# MakePython_Audio_v2_0.net
KiCad netlist of a schematic drawn in EAGLE
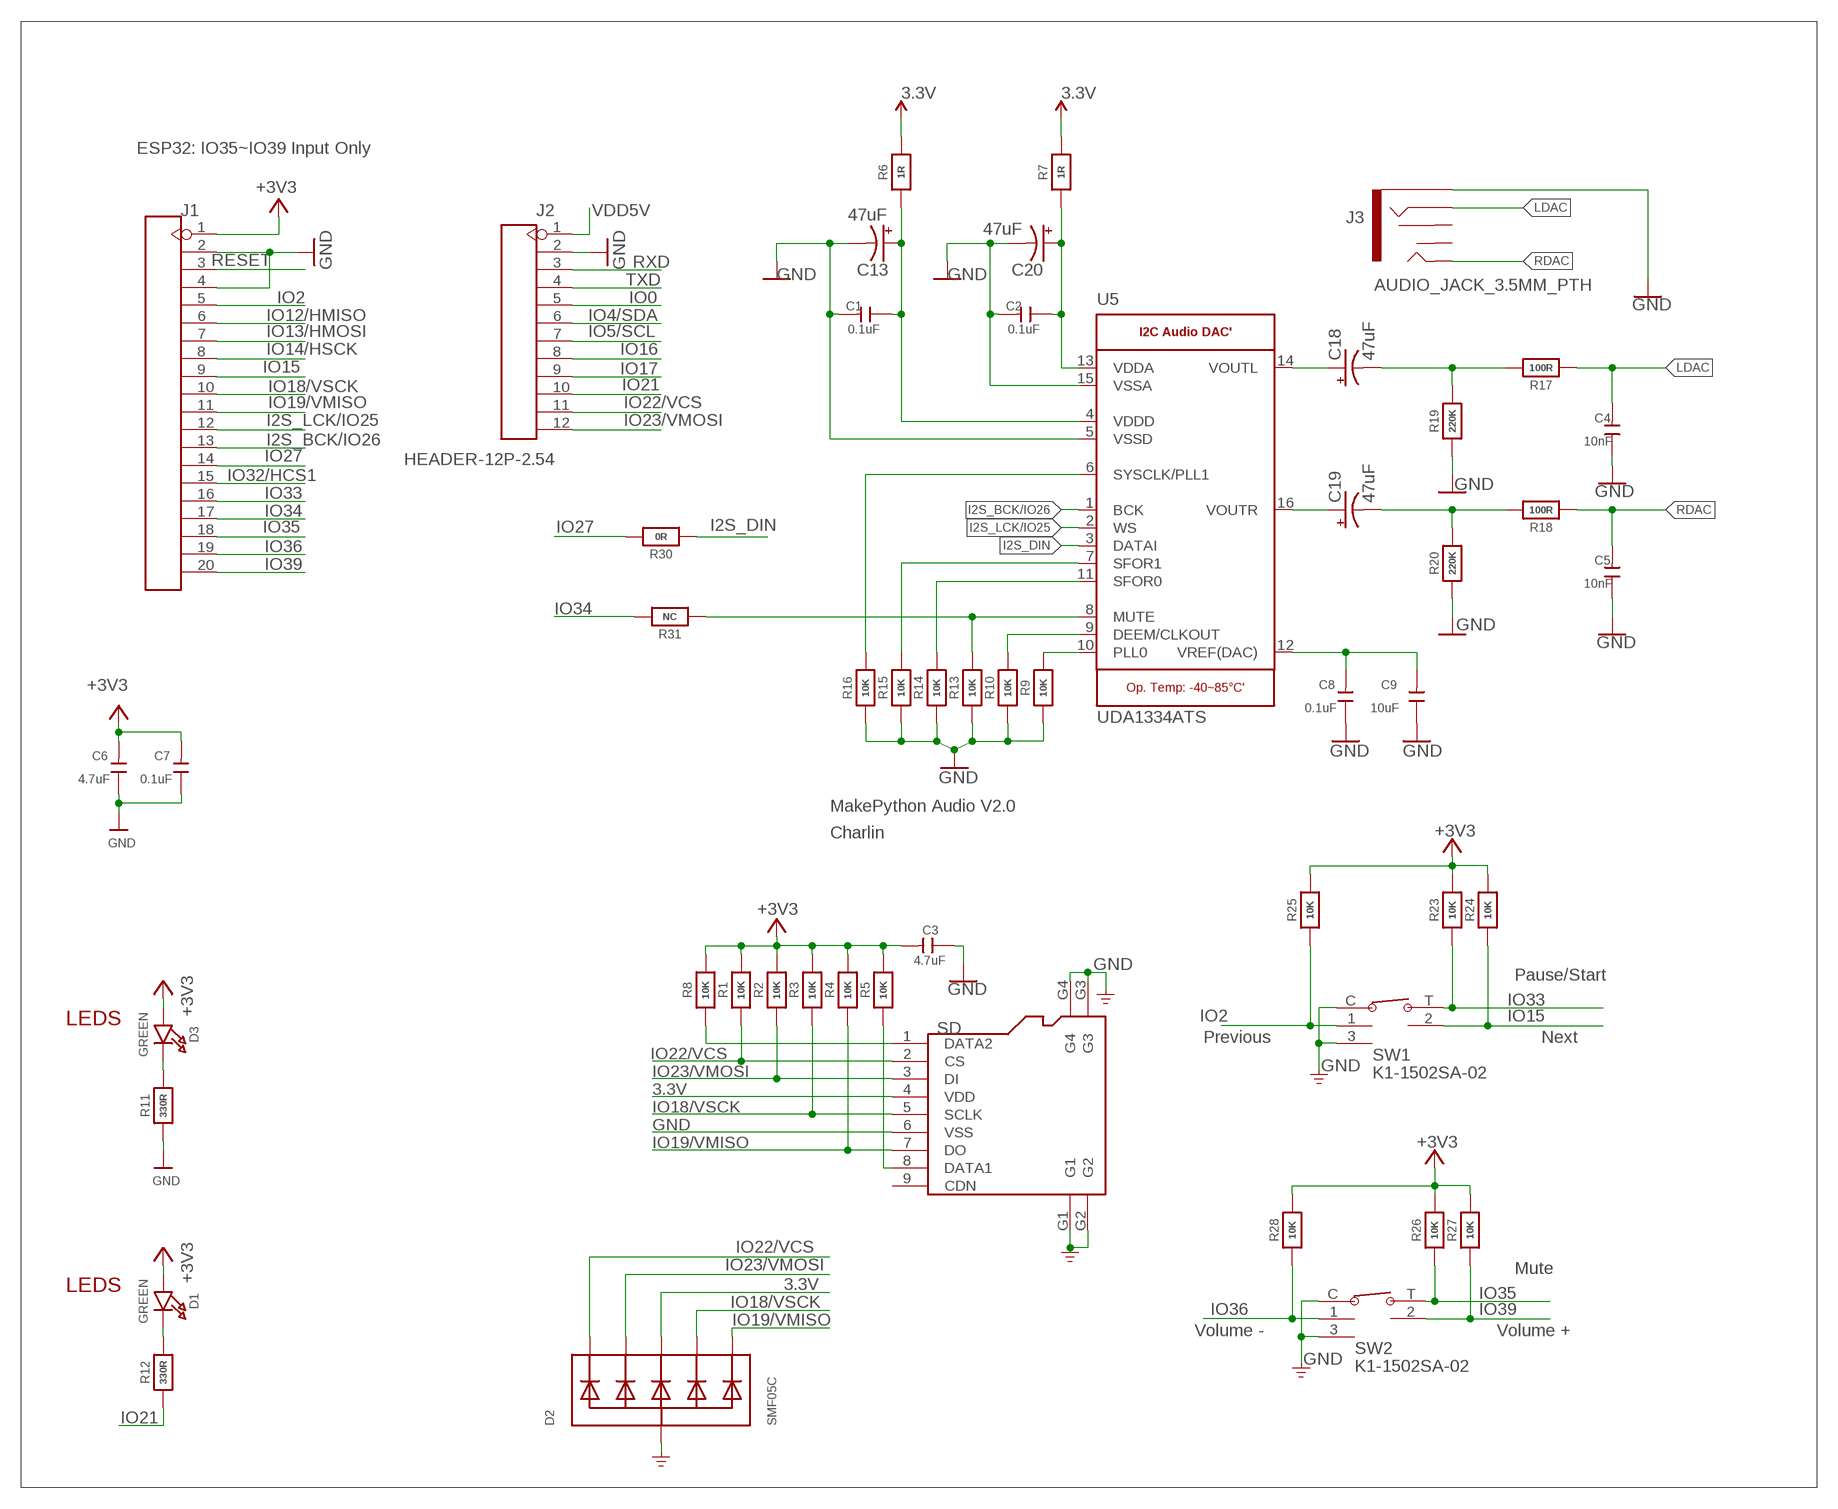
[diagram p0: schematic, sheet 1]

(export (version "E")
  (design (tool "Eeschema 10.0.6"))
  (components
    (comp (ref "C1")
      (value "0.1uF")
      (footprint "eagle-import:DISCRETE_C0603")
      (libsource (lib "eagle-import") (part "DISCRETE_C-0603"))
    )
    (comp (ref "C2")
      (value "0.1uF")
      (footprint "eagle-import:DISCRETE_C0603")
      (libsource (lib "eagle-import") (part "DISCRETE_C-0603"))
    )
    (comp (ref "C3")
      (value "4.7uF")
      (footprint "eagle-import:DISCRETE_C0603")
      (libsource (lib "eagle-import") (part "DISCRETE_C-0603"))
    )
    (comp (ref "C4")
      (value "10nF")
      (footprint "eagle-import:DISCRETE_C0603")
      (libsource (lib "eagle-import") (part "DISCRETE_C-0603"))
    )
    (comp (ref "C5")
      (value "10nF")
      (footprint "eagle-import:DISCRETE_C0603")
      (libsource (lib "eagle-import") (part "DISCRETE_C-0603"))
    )
    (comp (ref "C6")
      (value "4.7uF")
      (footprint "eagle-import:DISCRETE_C0603")
      (libsource (lib "eagle-import") (part "DISCRETE_C-0603"))
    )
    (comp (ref "C7")
      (value "0.1uF")
      (footprint "eagle-import:DISCRETE_C0603")
      (libsource (lib "eagle-import") (part "DISCRETE_C-0603"))
    )
    (comp (ref "C8")
      (value "0.1uF")
      (footprint "eagle-import:DISCRETE_C0603")
      (libsource (lib "eagle-import") (part "DISCRETE_C-0603"))
    )
    (comp (ref "C9")
      (value "10uF")
      (footprint "eagle-import:DISCRETE_C0603")
      (libsource (lib "eagle-import") (part "DISCRETE_C-0603"))
    )
    (comp (ref "C13")
      (value "47uF")
      (footprint "eagle-import:EIA3528")
      (libsource (lib "eagle-import") (part "47UF-POLAR-EIA3528-10V-10%"))
    )
    (comp (ref "C18")
      (value "47uF")
      (footprint "eagle-import:EIA3528")
      (libsource (lib "eagle-import") (part "47UF-POLAR-EIA3528-10V-10%"))
    )
    (comp (ref "C19")
      (value "47uF")
      (footprint "eagle-import:EIA3528")
      (libsource (lib "eagle-import") (part "47UF-POLAR-EIA3528-10V-10%"))
    )
    (comp (ref "C20")
      (value "47uF")
      (footprint "eagle-import:EIA3528")
      (libsource (lib "eagle-import") (part "47UF-POLAR-EIA3528-10V-10%"))
    )
    (comp (ref "D1")
      (value "GREEN")
      (footprint "eagle-import:CHIPLED_0805_NOOUTLINE")
      (libsource (lib "eagle-import") (part "LED0805_NOOUTLINE"))
    )
    (comp (ref "D2")
      (value "SMF05C")
      (footprint "eagle-import:SOT363")
      (libsource (lib "eagle-import") (part "TVSARRAY_5LANE"))
    )
    (comp (ref "D3")
      (value "GREEN")
      (footprint "eagle-import:CHIPLED_0805_NOOUTLINE")
      (libsource (lib "eagle-import") (part "LED0805_NOOUTLINE"))
    )
    (comp (ref "J1")
      (value "HEADER-20P-2.54")
      (footprint "eagle-import:20P-2.54")
      (libsource (lib "eagle-import") (part "HEADER-20P-2.54"))
    )
    (comp (ref "J2")
      (value "HEADER-12P-2.54")
      (footprint "eagle-import:12P-2.54")
      (libsource (lib "eagle-import") (part "HEADER-12P-2.54"))
    )
    (comp (ref "J3")
      (value "AUDIO_JACK_3.5MM_PTH")
      (footprint "eagle-import:AUDIO-JACK")
      (libsource (lib "eagle-import") (part "AUDIO_JACK_3.5MM_PTH"))
    )
    (comp (ref "R1")
      (value "10K")
      (footprint "eagle-import:0603-NO")
      (libsource (lib "eagle-import") (part "RESISTOR_0603_NOOUT"))
    )
    (comp (ref "R2")
      (value "10K")
      (footprint "eagle-import:0603-NO")
      (libsource (lib "eagle-import") (part "RESISTOR_0603_NOOUT"))
    )
    (comp (ref "R3")
      (value "10K")
      (footprint "eagle-import:0603-NO")
      (libsource (lib "eagle-import") (part "RESISTOR_0603_NOOUT"))
    )
    (comp (ref "R4")
      (value "10K")
      (footprint "eagle-import:0603-NO")
      (libsource (lib "eagle-import") (part "RESISTOR_0603_NOOUT"))
    )
    (comp (ref "R5")
      (value "10K")
      (footprint "eagle-import:0603-NO")
      (libsource (lib "eagle-import") (part "RESISTOR_0603_NOOUT"))
    )
    (comp (ref "R6")
      (value "1R")
      (footprint "eagle-import:0603-NO")
      (libsource (lib "eagle-import") (part "RESISTOR_0603_NOOUT"))
    )
    (comp (ref "R7")
      (value "1R")
      (footprint "eagle-import:0603-NO")
      (libsource (lib "eagle-import") (part "RESISTOR_0603_NOOUT"))
    )
    (comp (ref "R8")
      (value "10K")
      (footprint "eagle-import:0603-NO")
      (libsource (lib "eagle-import") (part "RESISTOR_0603_NOOUT"))
    )
    (comp (ref "R9")
      (value "10K")
      (footprint "eagle-import:0603-NO")
      (libsource (lib "eagle-import") (part "RESISTOR_0603_NOOUT"))
    )
    (comp (ref "R10")
      (value "10K")
      (footprint "eagle-import:0603-NO")
      (libsource (lib "eagle-import") (part "RESISTOR_0603_NOOUT"))
    )
    (comp (ref "R11")
      (value "330R")
      (footprint "eagle-import:0603-NO")
      (libsource (lib "eagle-import") (part "RESISTOR_0603_NOOUT"))
    )
    (comp (ref "R12")
      (value "330R")
      (footprint "eagle-import:0603-NO")
      (libsource (lib "eagle-import") (part "RESISTOR_0603_NOOUT"))
    )
    (comp (ref "R13")
      (value "10K")
      (footprint "eagle-import:0603-NO")
      (libsource (lib "eagle-import") (part "RESISTOR_0603_NOOUT"))
    )
    (comp (ref "R14")
      (value "10K")
      (footprint "eagle-import:0603-NO")
      (libsource (lib "eagle-import") (part "RESISTOR_0603_NOOUT"))
    )
    (comp (ref "R15")
      (value "10K")
      (footprint "eagle-import:0603-NO")
      (libsource (lib "eagle-import") (part "RESISTOR_0603_NOOUT"))
    )
    (comp (ref "R16")
      (value "10K")
      (footprint "eagle-import:0603-NO")
      (libsource (lib "eagle-import") (part "RESISTOR_0603_NOOUT"))
    )
    (comp (ref "R17")
      (value "100R")
      (footprint "eagle-import:0603-NO")
      (libsource (lib "eagle-import") (part "RESISTOR_0603_NOOUT"))
    )
    (comp (ref "R18")
      (value "100R")
      (footprint "eagle-import:0603-NO")
      (libsource (lib "eagle-import") (part "RESISTOR_0603_NOOUT"))
    )
    (comp (ref "R19")
      (value "220K")
      (footprint "eagle-import:0603-NO")
      (libsource (lib "eagle-import") (part "RESISTOR_0603_NOOUT"))
    )
    (comp (ref "R20")
      (value "220K")
      (footprint "eagle-import:0603-NO")
      (libsource (lib "eagle-import") (part "RESISTOR_0603_NOOUT"))
    )
    (comp (ref "R23")
      (value "10K")
      (footprint "eagle-import:0603-NO")
      (libsource (lib "eagle-import") (part "RESISTOR_0603_NOOUT"))
    )
    (comp (ref "R24")
      (value "10K")
      (footprint "eagle-import:0603-NO")
      (libsource (lib "eagle-import") (part "RESISTOR_0603_NOOUT"))
    )
    (comp (ref "R25")
      (value "10K")
      (footprint "eagle-import:0603-NO")
      (libsource (lib "eagle-import") (part "RESISTOR_0603_NOOUT"))
    )
    (comp (ref "R26")
      (value "10K")
      (footprint "eagle-import:0603-NO")
      (libsource (lib "eagle-import") (part "RESISTOR_0603_NOOUT"))
    )
    (comp (ref "R27")
      (value "10K")
      (footprint "eagle-import:0603-NO")
      (libsource (lib "eagle-import") (part "RESISTOR_0603_NOOUT"))
    )
    (comp (ref "R28")
      (value "10K")
      (footprint "eagle-import:0603-NO")
      (libsource (lib "eagle-import") (part "RESISTOR_0603_NOOUT"))
    )
    (comp (ref "R30")
      (value "0R")
      (footprint "eagle-import:0603-NO")
      (libsource (lib "eagle-import") (part "RESISTOR_0603_NOOUT"))
    )
    (comp (ref "R31")
      (value "NC")
      (footprint "eagle-import:0603-NO")
      (libsource (lib "eagle-import") (part "RESISTOR_0603_NOOUT"))
    )
    (comp (ref "SD")
      (value "HOLDER-MICROSD-9P")
      (footprint "eagle-import:9P-SMD-W_-RING")
      (libsource (lib "eagle-import") (part "HOLDER-MICROSD-9P"))
    )
    (comp (ref "SW1")
      (value "K1-1502SA-02")
      (footprint "eagle-import:SMD5-60P-1180L1170W")
      (libsource (lib "eagle-import") (part "K1-1502SA-02"))
    )
    (comp (ref "SW2")
      (value "K1-1502SA-02")
      (footprint "eagle-import:SMD5-60P-1180L1170W")
      (libsource (lib "eagle-import") (part "K1-1502SA-02"))
    )
    (comp (ref "U5")
      (value "UDA1334ATS")
      (footprint "eagle-import:MICROBUILDER_SSOP16_4.4MM")
      (libsource (lib "eagle-import") (part "MICROBUILDER_AUDIO_I2S_UDA1334{dblquote}{dblquote}"))
    )
  )
  (nets
    (net (code "1") (name "+3V3") (class "Default")
      (node (ref "C3") (pin "2") (pinfunction "2_2") (pintype "passive"))
      (node (ref "C6") (pin "2") (pinfunction "2_2") (pintype "passive"))
      (node (ref "C7") (pin "2") (pinfunction "2_2") (pintype "passive"))
      (node (ref "D1") (pin "A") (pinfunction "A_A") (pintype "passive"))
      (node (ref "D2") (pin "4") (pinfunction "C3_4") (pintype "passive"))
      (node (ref "D3") (pin "A") (pinfunction "A_A") (pintype "passive"))
      (node (ref "J1") (pin "1") (pinfunction "P$1_1") (pintype "bidirectional"))
      (node (ref "R1") (pin "2") (pinfunction "2_2") (pintype "passive"))
      (node (ref "R2") (pin "2") (pinfunction "2_2") (pintype "passive"))
      (node (ref "R23") (pin "2") (pinfunction "2_2") (pintype "passive"))
      (node (ref "R24") (pin "2") (pinfunction "2_2") (pintype "passive"))
      (node (ref "R25") (pin "2") (pinfunction "2_2") (pintype "passive"))
      (node (ref "R26") (pin "2") (pinfunction "2_2") (pintype "passive"))
      (node (ref "R27") (pin "2") (pinfunction "2_2") (pintype "passive"))
      (node (ref "R28") (pin "2") (pinfunction "2_2") (pintype "passive"))
      (node (ref "R3") (pin "2") (pinfunction "2_2") (pintype "passive"))
      (node (ref "R4") (pin "2") (pinfunction "2_2") (pintype "passive"))
      (node (ref "R5") (pin "2") (pinfunction "2_2") (pintype "passive"))
      (node (ref "R6") (pin "2") (pinfunction "2_2") (pintype "passive"))
      (node (ref "R7") (pin "2") (pinfunction "2_2") (pintype "passive"))
      (node (ref "R8") (pin "2") (pinfunction "2_2") (pintype "passive"))
      (node (ref "SD") (pin "4") (pinfunction "VDD_4") (pintype "bidirectional"))
    )
    (net (code "2") (name "/IO0") (class "Default")
      (node (ref "J2") (pin "5") (pinfunction "5_5") (pintype "bidirectional"))
    )
    (net (code "3") (name "/IO2") (class "Default")
      (node (ref "J1") (pin "5") (pinfunction "P$5_5") (pintype "bidirectional"))
      (node (ref "R25") (pin "1") (pinfunction "1_1") (pintype "passive"))
      (node (ref "SW1") (pin "1") (pinfunction "1_1") (pintype "bidirectional"))
    )
    (net (code "4") (name "/IO4{slash}SDA") (class "Default")
      (node (ref "J2") (pin "6") (pinfunction "6_6") (pintype "bidirectional"))
    )
    (net (code "5") (name "/IO5{slash}SCL") (class "Default")
      (node (ref "J2") (pin "7") (pinfunction "7_7") (pintype "bidirectional"))
    )
    (net (code "6") (name "/IO12{slash}HMISO") (class "Default")
      (node (ref "J1") (pin "6") (pinfunction "P$6_6") (pintype "bidirectional"))
    )
    (net (code "7") (name "/IO13{slash}HMOSI") (class "Default")
      (node (ref "J1") (pin "7") (pinfunction "P$7_7") (pintype "bidirectional"))
    )
    (net (code "8") (name "/IO14{slash}HSCK") (class "Default")
      (node (ref "J1") (pin "8") (pinfunction "P$8_8") (pintype "bidirectional"))
    )
    (net (code "9") (name "/IO15") (class "Default")
      (node (ref "J1") (pin "9") (pinfunction "P$9_9") (pintype "bidirectional"))
      (node (ref "R24") (pin "1") (pinfunction "1_1") (pintype "passive"))
      (node (ref "SW1") (pin "2") (pinfunction "2_2") (pintype "bidirectional"))
    )
    (net (code "10") (name "/IO16") (class "Default")
      (node (ref "J2") (pin "8") (pinfunction "8_8") (pintype "bidirectional"))
    )
    (net (code "11") (name "/IO17") (class "Default")
      (node (ref "J2") (pin "9") (pinfunction "9_9") (pintype "bidirectional"))
    )
    (net (code "12") (name "/IO18{slash}VSCK") (class "Default")
      (node (ref "D2") (pin "5") (pinfunction "C4_5") (pintype "passive"))
      (node (ref "J1") (pin "10") (pinfunction "P$10_10") (pintype "bidirectional"))
      (node (ref "R3") (pin "1") (pinfunction "1_1") (pintype "passive"))
      (node (ref "SD") (pin "5") (pinfunction "SCLK_5") (pintype "bidirectional"))
    )
    (net (code "13") (name "/IO19{slash}VMISO") (class "Default")
      (node (ref "D2") (pin "6") (pinfunction "C5_6") (pintype "passive"))
      (node (ref "J1") (pin "11") (pinfunction "P$11_11") (pintype "bidirectional"))
      (node (ref "R4") (pin "1") (pinfunction "1_1") (pintype "passive"))
      (node (ref "SD") (pin "7") (pinfunction "DO_7") (pintype "bidirectional"))
    )
    (net (code "14") (name "/IO21") (class "Default")
      (node (ref "J2") (pin "10") (pinfunction "10_10") (pintype "bidirectional"))
      (node (ref "R12") (pin "1") (pinfunction "1_1") (pintype "passive"))
    )
    (net (code "15") (name "/IO22{slash}VCS") (class "Default")
      (node (ref "D2") (pin "1") (pinfunction "C1_1") (pintype "passive"))
      (node (ref "J2") (pin "11") (pinfunction "11_11") (pintype "bidirectional"))
      (node (ref "R1") (pin "1") (pinfunction "1_1") (pintype "passive"))
      (node (ref "SD") (pin "2") (pinfunction "CS_2") (pintype "bidirectional"))
    )
    (net (code "16") (name "/IO23{slash}VMOSI") (class "Default")
      (node (ref "D2") (pin "3") (pinfunction "C2_3") (pintype "passive"))
      (node (ref "J2") (pin "12") (pinfunction "12_12") (pintype "bidirectional"))
      (node (ref "R2") (pin "1") (pinfunction "1_1") (pintype "passive"))
      (node (ref "SD") (pin "3") (pinfunction "DI_3") (pintype "bidirectional"))
    )
    (net (code "17") (name "/IO27") (class "Default")
      (node (ref "J1") (pin "14") (pinfunction "P$14_14") (pintype "bidirectional"))
      (node (ref "R30") (pin "2") (pinfunction "2_2") (pintype "passive"))
    )
    (net (code "18") (name "/IO32{slash}HCS1") (class "Default")
      (node (ref "J1") (pin "15") (pinfunction "P$15_15") (pintype "bidirectional"))
    )
    (net (code "19") (name "/IO33") (class "Default")
      (node (ref "J1") (pin "16") (pinfunction "P$16_16") (pintype "bidirectional"))
      (node (ref "R23") (pin "1") (pinfunction "1_1") (pintype "passive"))
      (node (ref "SW1") (pin "T") (pinfunction "T_T") (pintype "bidirectional"))
    )
    (net (code "20") (name "/IO34") (class "Default")
      (node (ref "J1") (pin "17") (pinfunction "P$17_17") (pintype "bidirectional"))
      (node (ref "R31") (pin "2") (pinfunction "2_2") (pintype "passive"))
    )
    (net (code "21") (name "/IO35") (class "Default")
      (node (ref "J1") (pin "18") (pinfunction "P$18_18") (pintype "bidirectional"))
      (node (ref "R26") (pin "1") (pinfunction "1_1") (pintype "passive"))
      (node (ref "SW2") (pin "T") (pinfunction "T_T") (pintype "bidirectional"))
    )
    (net (code "22") (name "/IO36") (class "Default")
      (node (ref "J1") (pin "19") (pinfunction "P$19_19") (pintype "bidirectional"))
      (node (ref "R28") (pin "1") (pinfunction "1_1") (pintype "passive"))
      (node (ref "SW2") (pin "1") (pinfunction "1_1") (pintype "bidirectional"))
    )
    (net (code "23") (name "/IO39") (class "Default")
      (node (ref "J1") (pin "20") (pinfunction "P$20_20") (pintype "bidirectional"))
      (node (ref "R27") (pin "1") (pinfunction "1_1") (pintype "passive"))
      (node (ref "SW2") (pin "2") (pinfunction "2_2") (pintype "bidirectional"))
    )
    (net (code "24") (name "/RESET") (class "Default")
      (node (ref "J1") (pin "3") (pinfunction "P$3_3") (pintype "bidirectional"))
    )
    (net (code "25") (name "/RXD") (class "Default")
      (node (ref "J2") (pin "3") (pinfunction "3_3") (pintype "bidirectional"))
    )
    (net (code "26") (name "/TXD") (class "Default")
      (node (ref "J2") (pin "4") (pinfunction "4_4") (pintype "bidirectional"))
    )
    (net (code "27") (name "/VDD5V") (class "Default")
      (node (ref "J2") (pin "1") (pinfunction "1_1") (pintype "bidirectional"))
    )
    (net (code "28") (name "GND") (class "Default")
      (node (ref "C1") (pin "2") (pinfunction "2_2") (pintype "passive"))
      (node (ref "C13") (pin "C") (pinfunction "-_C") (pintype "passive"))
      (node (ref "C2") (pin "2") (pinfunction "2_2") (pintype "passive"))
      (node (ref "C20") (pin "C") (pinfunction "-_C") (pintype "passive"))
      (node (ref "C3") (pin "1") (pinfunction "1_1") (pintype "passive"))
      (node (ref "C4") (pin "1") (pinfunction "1_1") (pintype "passive"))
      (node (ref "C5") (pin "1") (pinfunction "1_1") (pintype "passive"))
      (node (ref "C6") (pin "1") (pinfunction "1_1") (pintype "passive"))
      (node (ref "C7") (pin "1") (pinfunction "1_1") (pintype "passive"))
      (node (ref "C8") (pin "1") (pinfunction "1_1") (pintype "passive"))
      (node (ref "C9") (pin "1") (pinfunction "1_1") (pintype "passive"))
      (node (ref "D2") (pin "2") (pinfunction "A_2") (pintype "passive"))
      (node (ref "J1") (pin "2") (pinfunction "P$2_2") (pintype "bidirectional"))
      (node (ref "J1") (pin "4") (pinfunction "P$4_4") (pintype "bidirectional"))
      (node (ref "J2") (pin "2") (pinfunction "2_2") (pintype "bidirectional"))
      (node (ref "J3") (pin "SLEEVE") (pinfunction "SLEEVE_SLEEVE") (pintype "bidirectional"))
      (node (ref "R10") (pin "1") (pinfunction "1_1") (pintype "passive"))
      (node (ref "R11") (pin "1") (pinfunction "1_1") (pintype "passive"))
      (node (ref "R13") (pin "1") (pinfunction "1_1") (pintype "passive"))
      (node (ref "R14") (pin "1") (pinfunction "1_1") (pintype "passive"))
      (node (ref "R15") (pin "1") (pinfunction "1_1") (pintype "passive"))
      (node (ref "R16") (pin "1") (pinfunction "1_1") (pintype "passive"))
      (node (ref "R19") (pin "1") (pinfunction "1_1") (pintype "passive"))
      (node (ref "R20") (pin "1") (pinfunction "1_1") (pintype "passive"))
      (node (ref "R9") (pin "1") (pinfunction "1_1") (pintype "passive"))
      (node (ref "SD") (pin "6") (pinfunction "VSS_6") (pintype "bidirectional"))
      (node (ref "SD") (pin "G1") (pinfunction "G1_G1") (pintype "bidirectional"))
      (node (ref "SD") (pin "G2") (pinfunction "G2_G2") (pintype "bidirectional"))
      (node (ref "SD") (pin "G3") (pinfunction "G3_G3") (pintype "bidirectional"))
      (node (ref "SD") (pin "G4") (pinfunction "G4_G4") (pintype "bidirectional"))
      (node (ref "SW1") (pin "3") (pinfunction "3_3") (pintype "bidirectional"))
      (node (ref "SW1") (pin "C") (pinfunction "C_C") (pintype "bidirectional"))
      (node (ref "SW2") (pin "3") (pinfunction "3_3") (pintype "bidirectional"))
      (node (ref "SW2") (pin "C") (pinfunction "C_C") (pintype "bidirectional"))
      (node (ref "U5") (pin "15") (pinfunction "VSSA_15") (pintype "power_in"))
      (node (ref "U5") (pin "5") (pinfunction "VSSD_5") (pintype "power_in"))
    )
    (net (code "29") (name "I2S_BCK{slash}IO26") (class "Default")
      (node (ref "J1") (pin "13") (pinfunction "P$13_13") (pintype "bidirectional"))
      (node (ref "U5") (pin "1") (pinfunction "BCK_1") (pintype "input"))
    )
    (net (code "30") (name "I2S_DIN") (class "Default")
      (node (ref "R30") (pin "1") (pinfunction "1_1") (pintype "passive"))
      (node (ref "U5") (pin "3") (pinfunction "DATAI_3") (pintype "input"))
    )
    (net (code "31") (name "I2S_LCK{slash}IO25") (class "Default")
      (node (ref "J1") (pin "12") (pinfunction "P$12_12") (pintype "bidirectional"))
      (node (ref "U5") (pin "2") (pinfunction "WS_2") (pintype "input"))
    )
    (net (code "32") (name "LDAC") (class "Default")
      (node (ref "C4") (pin "2") (pinfunction "2_2") (pintype "passive"))
      (node (ref "J3") (pin "RING") (pinfunction "RING_RING") (pintype "bidirectional"))
      (node (ref "R17") (pin "1") (pinfunction "1_1") (pintype "passive"))
    )
    (net (code "33") (name "Net-(C13-+)") (class "Default")
      (node (ref "C1") (pin "1") (pinfunction "1_1") (pintype "passive"))
      (node (ref "C13") (pin "A") (pinfunction "+_A") (pintype "passive"))
      (node (ref "R6") (pin "1") (pinfunction "1_1") (pintype "passive"))
      (node (ref "U5") (pin "4") (pinfunction "VDDD_4") (pintype "power_in"))
    )
    (net (code "34") (name "Net-(C18-+)") (class "Default")
      (node (ref "C18") (pin "A") (pinfunction "+_A") (pintype "passive"))
      (node (ref "U5") (pin "14") (pinfunction "VOUTL_14") (pintype "output"))
    )
    (net (code "35") (name "Net-(C18--)") (class "Default")
      (node (ref "C18") (pin "C") (pinfunction "-_C") (pintype "passive"))
      (node (ref "R17") (pin "2") (pinfunction "2_2") (pintype "passive"))
      (node (ref "R19") (pin "2") (pinfunction "2_2") (pintype "passive"))
    )
    (net (code "36") (name "Net-(C19-+)") (class "Default")
      (node (ref "C19") (pin "A") (pinfunction "+_A") (pintype "passive"))
      (node (ref "U5") (pin "16") (pinfunction "VOUTR_16") (pintype "output"))
    )
    (net (code "37") (name "Net-(C19--)") (class "Default")
      (node (ref "C19") (pin "C") (pinfunction "-_C") (pintype "passive"))
      (node (ref "R18") (pin "2") (pinfunction "2_2") (pintype "passive"))
      (node (ref "R20") (pin "2") (pinfunction "2_2") (pintype "passive"))
    )
    (net (code "38") (name "Net-(C20-+)") (class "Default")
      (node (ref "C2") (pin "1") (pinfunction "1_1") (pintype "passive"))
      (node (ref "C20") (pin "A") (pinfunction "+_A") (pintype "passive"))
      (node (ref "R7") (pin "1") (pinfunction "1_1") (pintype "passive"))
      (node (ref "U5") (pin "13") (pinfunction "VDDA_13") (pintype "power_in"))
    )
    (net (code "39") (name "Net-(D1-PadC)") (class "Default")
      (node (ref "D1") (pin "C") (pinfunction "C_C") (pintype "passive"))
      (node (ref "R12") (pin "2") (pinfunction "2_2") (pintype "passive"))
    )
    (net (code "40") (name "Net-(D3-PadC)") (class "Default")
      (node (ref "D3") (pin "C") (pinfunction "C_C") (pintype "passive"))
      (node (ref "R11") (pin "2") (pinfunction "2_2") (pintype "passive"))
    )
    (net (code "41") (name "Net-(SD-DATA1)") (class "Default")
      (node (ref "R5") (pin "1") (pinfunction "1_1") (pintype "passive"))
      (node (ref "SD") (pin "8") (pinfunction "DATA1_8") (pintype "bidirectional"))
    )
    (net (code "42") (name "Net-(SD-DATA2)") (class "Default")
      (node (ref "R8") (pin "1") (pinfunction "1_1") (pintype "passive"))
      (node (ref "SD") (pin "1") (pinfunction "DATA2_1") (pintype "bidirectional"))
    )
    (net (code "43") (name "Net-(U5-DEEM{slash}CLKOUT)") (class "Default")
      (node (ref "R10") (pin "2") (pinfunction "2_2") (pintype "passive"))
      (node (ref "U5") (pin "9") (pinfunction "DEEM/CLKOUT_9") (pintype "bidirectional"))
    )
    (net (code "44") (name "Net-(U5-MUTE)") (class "Default")
      (node (ref "R13") (pin "2") (pinfunction "2_2") (pintype "passive"))
      (node (ref "R31") (pin "1") (pinfunction "1_1") (pintype "passive"))
      (node (ref "U5") (pin "8") (pinfunction "MUTE_8") (pintype "input"))
    )
    (net (code "45") (name "Net-(U5-PLL0)") (class "Default")
      (node (ref "R9") (pin "2") (pinfunction "2_2") (pintype "passive"))
      (node (ref "U5") (pin "10") (pinfunction "PLL0_10") (pintype "input"))
    )
    (net (code "46") (name "Net-(U5-SFOR0)") (class "Default")
      (node (ref "R14") (pin "2") (pinfunction "2_2") (pintype "passive"))
      (node (ref "U5") (pin "11") (pinfunction "SFOR0_11") (pintype "input"))
    )
    (net (code "47") (name "Net-(U5-SFOR1)") (class "Default")
      (node (ref "R15") (pin "2") (pinfunction "2_2") (pintype "passive"))
      (node (ref "U5") (pin "7") (pinfunction "SFOR1_7") (pintype "input"))
    )
    (net (code "48") (name "Net-(U5-SYSCLK{slash}PLL1)") (class "Default")
      (node (ref "R16") (pin "2") (pinfunction "2_2") (pintype "passive"))
      (node (ref "U5") (pin "6") (pinfunction "SYSCLK/PLL1_6") (pintype "input"))
    )
    (net (code "49") (name "Net-(U5-VREF(DAC))") (class "Default")
      (node (ref "C8") (pin "2") (pinfunction "2_2") (pintype "passive"))
      (node (ref "C9") (pin "2") (pinfunction "2_2") (pintype "passive"))
      (node (ref "U5") (pin "12") (pinfunction "VREF(DAC)_12") (pintype "output"))
    )
    (net (code "50") (name "RDAC") (class "Default")
      (node (ref "C5") (pin "2") (pinfunction "2_2") (pintype "passive"))
      (node (ref "J3") (pin "TIP") (pinfunction "TIP_TIP") (pintype "bidirectional"))
      (node (ref "R18") (pin "1") (pinfunction "1_1") (pintype "passive"))
    )
    (net (code "51") (name "unconnected-(J3-PadRSH)") (class "Default")
      (node (ref "J3") (pin "RSH") (pinfunction "RSH_RSH") (pintype "bidirectional"))
    )
    (net (code "52") (name "unconnected-(J3-PadTSH)") (class "Default")
      (node (ref "J3") (pin "TSH") (pinfunction "TSH_TSH") (pintype "bidirectional"))
    )
    (net (code "53") (name "unconnected-(SD-CDN-Pad9)") (class "Default")
      (node (ref "SD") (pin "9") (pinfunction "CDN_9") (pintype "bidirectional"))
    )
  )
)
